# espcam.net
KiCad netlist of a schematic drawn in EAGLE
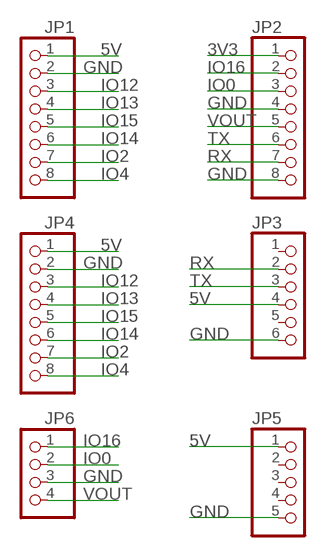
[diagram p0: schematic, sheet 1]

(export (version "E")
  (design (tool "Eeschema 10.0.6"))
  (components
    (comp (ref "JP1")
      (value "PINHD-1X8")
      (footprint "eagle-import:1X08")
      (libsource (lib "eagle-import") (part "PINHD-1X8"))
    )
    (comp (ref "JP2")
      (value "PINHD-1X8")
      (footprint "eagle-import:1X08")
      (libsource (lib "eagle-import") (part "PINHD-1X8"))
    )
    (comp (ref "JP3")
      (value "PINHD-1X6")
      (footprint "eagle-import:1X06")
      (libsource (lib "eagle-import") (part "PINHD-1X6"))
    )
    (comp (ref "JP4")
      (value "PINHD-1X8")
      (footprint "eagle-import:1X08")
      (libsource (lib "eagle-import") (part "PINHD-1X8"))
    )
    (comp (ref "JP5")
      (value "PINHD-1X5")
      (footprint "eagle-import:1X05")
      (libsource (lib "eagle-import") (part "PINHD-1X5"))
    )
    (comp (ref "JP6")
      (value "PINHD-1X4")
      (footprint "eagle-import:1X04")
      (libsource (lib "eagle-import") (part "PINHD-1X4"))
    )
  )
  (nets
    (net (code "1") (name "/3V3") (class "Default")
      (node (ref "JP2") (pin "1") (pinfunction "1_1") (pintype "passive"))
    )
    (net (code "2") (name "/5V") (class "Default")
      (node (ref "JP1") (pin "1") (pinfunction "1_1") (pintype "passive"))
      (node (ref "JP3") (pin "4") (pinfunction "4_4") (pintype "passive"))
      (node (ref "JP4") (pin "1") (pinfunction "1_1") (pintype "passive"))
      (node (ref "JP5") (pin "1") (pinfunction "1_1") (pintype "passive"))
    )
    (net (code "3") (name "/GND") (class "Default")
      (node (ref "JP1") (pin "2") (pinfunction "2_2") (pintype "passive"))
      (node (ref "JP2") (pin "4") (pinfunction "4_4") (pintype "passive"))
      (node (ref "JP2") (pin "8") (pinfunction "8_8") (pintype "passive"))
      (node (ref "JP3") (pin "6") (pinfunction "6_6") (pintype "passive"))
      (node (ref "JP4") (pin "2") (pinfunction "2_2") (pintype "passive"))
      (node (ref "JP5") (pin "5") (pinfunction "5_5") (pintype "passive"))
      (node (ref "JP6") (pin "3") (pinfunction "3_3") (pintype "passive"))
    )
    (net (code "4") (name "/IO0") (class "Default")
      (node (ref "JP2") (pin "3") (pinfunction "3_3") (pintype "passive"))
      (node (ref "JP6") (pin "2") (pinfunction "2_2") (pintype "passive"))
    )
    (net (code "5") (name "/IO2") (class "Default")
      (node (ref "JP1") (pin "7") (pinfunction "7_7") (pintype "passive"))
      (node (ref "JP4") (pin "7") (pinfunction "7_7") (pintype "passive"))
    )
    (net (code "6") (name "/IO4") (class "Default")
      (node (ref "JP1") (pin "8") (pinfunction "8_8") (pintype "passive"))
      (node (ref "JP4") (pin "8") (pinfunction "8_8") (pintype "passive"))
    )
    (net (code "7") (name "/IO12") (class "Default")
      (node (ref "JP1") (pin "3") (pinfunction "3_3") (pintype "passive"))
      (node (ref "JP4") (pin "3") (pinfunction "3_3") (pintype "passive"))
    )
    (net (code "8") (name "/IO13") (class "Default")
      (node (ref "JP1") (pin "4") (pinfunction "4_4") (pintype "passive"))
      (node (ref "JP4") (pin "4") (pinfunction "4_4") (pintype "passive"))
    )
    (net (code "9") (name "/IO14") (class "Default")
      (node (ref "JP1") (pin "6") (pinfunction "6_6") (pintype "passive"))
      (node (ref "JP4") (pin "6") (pinfunction "6_6") (pintype "passive"))
    )
    (net (code "10") (name "/IO15") (class "Default")
      (node (ref "JP1") (pin "5") (pinfunction "5_5") (pintype "passive"))
      (node (ref "JP4") (pin "5") (pinfunction "5_5") (pintype "passive"))
    )
    (net (code "11") (name "/IO16") (class "Default")
      (node (ref "JP2") (pin "2") (pinfunction "2_2") (pintype "passive"))
      (node (ref "JP6") (pin "1") (pinfunction "1_1") (pintype "passive"))
    )
    (net (code "12") (name "/RX") (class "Default")
      (node (ref "JP2") (pin "7") (pinfunction "7_7") (pintype "passive"))
      (node (ref "JP3") (pin "2") (pinfunction "2_2") (pintype "passive"))
    )
    (net (code "13") (name "/TX") (class "Default")
      (node (ref "JP2") (pin "6") (pinfunction "6_6") (pintype "passive"))
      (node (ref "JP3") (pin "3") (pinfunction "3_3") (pintype "passive"))
    )
    (net (code "14") (name "/VOUT") (class "Default")
      (node (ref "JP2") (pin "5") (pinfunction "5_5") (pintype "passive"))
      (node (ref "JP6") (pin "4") (pinfunction "4_4") (pintype "passive"))
    )
    (net (code "15") (name "unconnected-(JP3-Pad1)") (class "Default")
      (node (ref "JP3") (pin "1") (pinfunction "1_1") (pintype "passive"))
    )
    (net (code "16") (name "unconnected-(JP3-Pad5)") (class "Default")
      (node (ref "JP3") (pin "5") (pinfunction "5_5") (pintype "passive"))
    )
    (net (code "17") (name "unconnected-(JP5-Pad2)") (class "Default")
      (node (ref "JP5") (pin "2") (pinfunction "2_2") (pintype "passive"))
    )
    (net (code "18") (name "unconnected-(JP5-Pad3)") (class "Default")
      (node (ref "JP5") (pin "3") (pinfunction "3_3") (pintype "passive"))
    )
    (net (code "19") (name "unconnected-(JP5-Pad4)") (class "Default")
      (node (ref "JP5") (pin "4") (pinfunction "4_4") (pintype "passive"))
    )
  )
)
